# Sheet1.net
KiCad netlist of a schematic drawn in Altium Designer
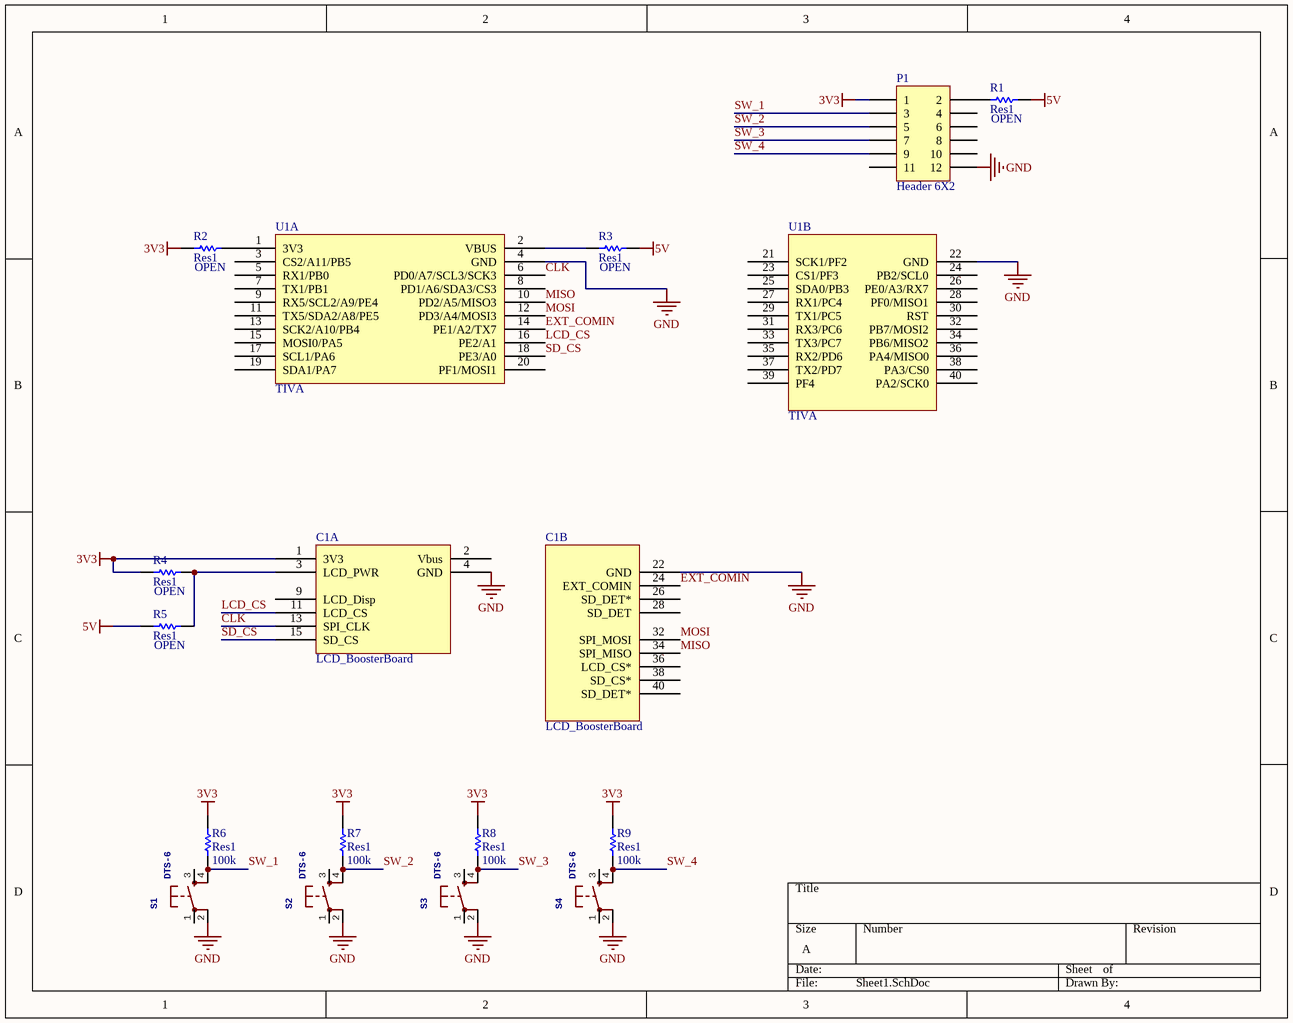
[diagram p0: Sheet1.SchDoc]

(export (version "E")
  (design (tool "Eeschema 10.0.6"))
  (components
    (comp (ref "C1")
      (value "LCD_BoosterBoard")
      (footprint "TIVA")
      (libsource (lib "Schlib1") (part "LCD_BoosterBoard"))
    )
    (comp (ref "P1")
      (value "Header 6X2")
      (footprint "HDR2X6")
      (description "Header, 6-Pin, Dual row")
      (fields (field (name "PUBLISHER") "Altium Limited"))
      (libsource (lib "Miscellaneous Connectors") (part "Header 6X2"))
    )
    (comp (ref "R1")
      (value "Res1")
      (footprint "AXIAL-0.3")
      (description "Resistor")
      (fields (field (name "ALTIUM_VALUE") "OPEN") (field (name "PUBLISHER") "Altium Limited"))
      (libsource (lib "Miscellaneous Devices") (part "Res1"))
    )
    (comp (ref "R2")
      (value "Res1")
      (footprint "AXIAL-0.3")
      (description "Resistor")
      (fields (field (name "ALTIUM_VALUE") "OPEN") (field (name "PUBLISHER") "Altium Limited"))
      (libsource (lib "Miscellaneous Devices") (part "Res1"))
    )
    (comp (ref "R3")
      (value "Res1")
      (footprint "AXIAL-0.3")
      (description "Resistor")
      (fields (field (name "ALTIUM_VALUE") "OPEN") (field (name "PUBLISHER") "Altium Limited"))
      (libsource (lib "Miscellaneous Devices") (part "Res1"))
    )
    (comp (ref "R4")
      (value "Res1")
      (footprint "AXIAL-0.3")
      (description "Resistor")
      (fields (field (name "ALTIUM_VALUE") "OPEN") (field (name "PUBLISHER") "Altium Limited"))
      (libsource (lib "Miscellaneous Devices") (part "Res1"))
    )
    (comp (ref "R5")
      (value "Res1")
      (footprint "AXIAL-0.3")
      (description "Resistor")
      (fields (field (name "ALTIUM_VALUE") "OPEN") (field (name "PUBLISHER") "Altium Limited"))
      (libsource (lib "Miscellaneous Devices") (part "Res1"))
    )
    (comp (ref "R6")
      (value "Res1")
      (footprint "AXIAL-0.3")
      (description "Resistor")
      (fields (field (name "ALTIUM_VALUE") "100k") (field (name "PUBLISHER") "Altium Limited"))
      (libsource (lib "Miscellaneous Devices") (part "Res1"))
    )
    (comp (ref "R7")
      (value "Res1")
      (footprint "AXIAL-0.3")
      (description "Resistor")
      (fields (field (name "ALTIUM_VALUE") "100k") (field (name "PUBLISHER") "Altium Limited"))
      (libsource (lib "Miscellaneous Devices") (part "Res1"))
    )
    (comp (ref "R8")
      (value "Res1")
      (footprint "AXIAL-0.3")
      (description "Resistor")
      (fields (field (name "ALTIUM_VALUE") "100k") (field (name "PUBLISHER") "Altium Limited"))
      (libsource (lib "Miscellaneous Devices") (part "Res1"))
    )
    (comp (ref "R9")
      (value "Res1")
      (footprint "AXIAL-0.3")
      (description "Resistor")
      (fields (field (name "ALTIUM_VALUE") "100k") (field (name "PUBLISHER") "Altium Limited"))
      (libsource (lib "Miscellaneous Devices") (part "Res1"))
    )
    (comp (ref "S1") (value "DTS-6") (footprint "DTS-6") (libsource (lib "Switches") (part "DTS-6")))
    (comp (ref "S2") (value "DTS-6") (footprint "DTS-6") (libsource (lib "Switches") (part "DTS-6")))
    (comp (ref "S3") (value "DTS-6") (footprint "DTS-6") (libsource (lib "Switches") (part "DTS-6")))
    (comp (ref "S4") (value "DTS-6") (footprint "DTS-6") (libsource (lib "Switches") (part "DTS-6")))
    (comp (ref "U1") (value "TIVA") (footprint "TIVA") (libsource (lib "Schlib1") (part "TIVA")))
  )
  (nets
    (net (code "1") (name "/CLK") (class "Default")
      (node (ref "C1") (pin "13") (pinfunction "SPI_CLK_13") (pintype "passive"))
      (node (ref "U1") (pin "6") (pinfunction "PD0/A7/SCL3/SCK3_6") (pintype "passive"))
    )
    (net (code "2") (name "/EXT_COMIN") (class "Default")
      (node (ref "C1") (pin "24") (pinfunction "EXT_COMIN_24") (pintype "passive"))
      (node (ref "U1") (pin "14") (pinfunction "PE1/A2/TX7_14") (pintype "passive"))
    )
    (net (code "3") (name "/LCD_CS") (class "Default")
      (node (ref "C1") (pin "11") (pinfunction "LCD_CS_11") (pintype "passive"))
      (node (ref "U1") (pin "16") (pinfunction "PE2/A1_16") (pintype "passive"))
    )
    (net (code "4") (name "/MISO") (class "Default")
      (node (ref "C1") (pin "34") (pinfunction "SPI_MISO_34") (pintype "passive"))
      (node (ref "U1") (pin "10") (pinfunction "PD2/A5/MISO3_10") (pintype "passive"))
    )
    (net (code "5") (name "/MOSI") (class "Default")
      (node (ref "C1") (pin "32") (pinfunction "SPI_MOSI_32") (pintype "passive"))
      (node (ref "U1") (pin "12") (pinfunction "PD3/A4/MOSI3_12") (pintype "passive"))
    )
    (net (code "6") (name "/SD_CS") (class "Default")
      (node (ref "C1") (pin "15") (pinfunction "SD_CS_15") (pintype "passive"))
      (node (ref "U1") (pin "18") (pinfunction "PE3/A0_18") (pintype "passive"))
    )
    (net (code "7") (name "/SW_1") (class "Default")
      (node (ref "P1") (pin "3") (pinfunction "3_3") (pintype "passive"))
      (node (ref "R6") (pin "1") (pinfunction "1_1") (pintype "passive"))
      (node (ref "S1") (pin "4") (pinfunction "4_4") (pintype "passive"))
    )
    (net (code "8") (name "/SW_2") (class "Default")
      (node (ref "P1") (pin "5") (pinfunction "5_5") (pintype "passive"))
      (node (ref "R7") (pin "1") (pinfunction "1_1") (pintype "passive"))
      (node (ref "S2") (pin "4") (pinfunction "4_4") (pintype "passive"))
    )
    (net (code "9") (name "/SW_3") (class "Default")
      (node (ref "P1") (pin "7") (pinfunction "7_7") (pintype "passive"))
      (node (ref "R8") (pin "1") (pinfunction "1_1") (pintype "passive"))
      (node (ref "S3") (pin "4") (pinfunction "4_4") (pintype "passive"))
    )
    (net (code "10") (name "/SW_4") (class "Default")
      (node (ref "P1") (pin "9") (pinfunction "9_9") (pintype "passive"))
      (node (ref "R9") (pin "1") (pinfunction "1_1") (pintype "passive"))
      (node (ref "S4") (pin "4") (pinfunction "4_4") (pintype "passive"))
    )
    (net (code "11") (name "3V3") (class "Default")
      (node (ref "C1") (pin "1") (pinfunction "3V3_1") (pintype "passive"))
      (node (ref "P1") (pin "1") (pinfunction "1_1") (pintype "passive"))
      (node (ref "R2") (pin "2") (pinfunction "2_2") (pintype "passive"))
      (node (ref "R4") (pin "2") (pinfunction "2_2") (pintype "passive"))
      (node (ref "R6") (pin "2") (pinfunction "2_2") (pintype "passive"))
      (node (ref "R7") (pin "2") (pinfunction "2_2") (pintype "passive"))
      (node (ref "R8") (pin "2") (pinfunction "2_2") (pintype "passive"))
      (node (ref "R9") (pin "2") (pinfunction "2_2") (pintype "passive"))
    )
    (net (code "12") (name "5V") (class "Default")
      (node (ref "R1") (pin "1") (pinfunction "1_1") (pintype "passive"))
      (node (ref "R3") (pin "1") (pinfunction "1_1") (pintype "passive"))
      (node (ref "R5") (pin "2") (pinfunction "2_2") (pintype "passive"))
    )
    (net (code "13") (name "GND") (class "Default")
      (node (ref "C1") (pin "22") (pinfunction "GND_22") (pintype "passive"))
      (node (ref "C1") (pin "4") (pinfunction "GND_4") (pintype "passive"))
      (node (ref "P1") (pin "12") (pinfunction "12_12") (pintype "passive"))
      (node (ref "S1") (pin "2") (pinfunction "2_2") (pintype "passive"))
      (node (ref "S2") (pin "2") (pinfunction "2_2") (pintype "passive"))
      (node (ref "S3") (pin "2") (pinfunction "2_2") (pintype "passive"))
      (node (ref "S4") (pin "2") (pinfunction "2_2") (pintype "passive"))
      (node (ref "U1") (pin "22") (pinfunction "GND_22") (pintype "passive"))
      (node (ref "U1") (pin "4") (pinfunction "GND_4") (pintype "passive"))
    )
    (net (code "14") (name "Net-(C1A-LCD_PWR)") (class "Default")
      (node (ref "C1") (pin "3") (pinfunction "LCD_PWR_3") (pintype "passive"))
      (node (ref "R4") (pin "1") (pinfunction "1_1") (pintype "passive"))
      (node (ref "R5") (pin "1") (pinfunction "1_1") (pintype "passive"))
    )
    (net (code "15") (name "Net-(P1-Pad2)") (class "Default")
      (node (ref "P1") (pin "2") (pinfunction "2_2") (pintype "passive"))
      (node (ref "R1") (pin "2") (pinfunction "2_2") (pintype "passive"))
    )
    (net (code "16") (name "Net-(U1A-3V3)") (class "Default")
      (node (ref "R2") (pin "1") (pinfunction "1_1") (pintype "passive"))
      (node (ref "U1") (pin "1") (pinfunction "3V3_1") (pintype "passive"))
    )
    (net (code "17") (name "Net-(U1A-VBUS)") (class "Default")
      (node (ref "R3") (pin "2") (pinfunction "2_2") (pintype "passive"))
      (node (ref "U1") (pin "2") (pinfunction "VBUS_2") (pintype "passive"))
    )
    (net (code "18") (name "unconnected-(C1A-LCD_Disp-Pad9)") (class "Default")
      (node (ref "C1") (pin "9") (pinfunction "LCD_Disp_9") (pintype "passive"))
    )
    (net (code "19") (name "unconnected-(C1A-Vbus-Pad2)") (class "Default")
      (node (ref "C1") (pin "2") (pinfunction "Vbus_2") (pintype "passive"))
    )
    (net (code "20") (name "unconnected-(C1B-LCD_CS*-Pad36)") (class "Default")
      (node (ref "C1") (pin "36") (pinfunction "LCD_CS*_36") (pintype "passive"))
    )
    (net (code "21") (name "unconnected-(C1B-SD_CS*-Pad38)") (class "Default")
      (node (ref "C1") (pin "38") (pinfunction "SD_CS*_38") (pintype "passive"))
    )
    (net (code "22") (name "unconnected-(C1B-SD_DET*-Pad26)") (class "Default")
      (node (ref "C1") (pin "26") (pinfunction "SD_DET*_26") (pintype "passive"))
    )
    (net (code "23") (name "unconnected-(C1B-SD_DET*-Pad40)") (class "Default")
      (node (ref "C1") (pin "40") (pinfunction "SD_DET*_40") (pintype "passive"))
    )
    (net (code "24") (name "unconnected-(C1B-SD_DET-Pad28)") (class "Default")
      (node (ref "C1") (pin "28") (pinfunction "SD_DET_28") (pintype "passive"))
    )
    (net (code "25") (name "unconnected-(P1-Pad4)") (class "Default")
      (node (ref "P1") (pin "4") (pinfunction "4_4") (pintype "passive"))
    )
    (net (code "26") (name "unconnected-(P1-Pad6)") (class "Default")
      (node (ref "P1") (pin "6") (pinfunction "6_6") (pintype "passive"))
    )
    (net (code "27") (name "unconnected-(P1-Pad8)") (class "Default")
      (node (ref "P1") (pin "8") (pinfunction "8_8") (pintype "passive"))
    )
    (net (code "28") (name "unconnected-(P1-Pad10)") (class "Default")
      (node (ref "P1") (pin "10") (pinfunction "10_10") (pintype "passive"))
    )
    (net (code "29") (name "unconnected-(P1-Pad11)") (class "Default")
      (node (ref "P1") (pin "11") (pinfunction "11_11") (pintype "passive"))
    )
    (net (code "30") (name "unconnected-(S1-Pad1)") (class "Default")
      (node (ref "S1") (pin "1") (pinfunction "1_1") (pintype "passive"))
    )
    (net (code "31") (name "unconnected-(S1-Pad3)") (class "Default")
      (node (ref "S1") (pin "3") (pinfunction "3_3") (pintype "passive"))
    )
    (net (code "32") (name "unconnected-(S2-Pad1)") (class "Default")
      (node (ref "S2") (pin "1") (pinfunction "1_1") (pintype "passive"))
    )
    (net (code "33") (name "unconnected-(S2-Pad3)") (class "Default")
      (node (ref "S2") (pin "3") (pinfunction "3_3") (pintype "passive"))
    )
    (net (code "34") (name "unconnected-(S3-Pad1)") (class "Default")
      (node (ref "S3") (pin "1") (pinfunction "1_1") (pintype "passive"))
    )
    (net (code "35") (name "unconnected-(S3-Pad3)") (class "Default")
      (node (ref "S3") (pin "3") (pinfunction "3_3") (pintype "passive"))
    )
    (net (code "36") (name "unconnected-(S4-Pad1)") (class "Default")
      (node (ref "S4") (pin "1") (pinfunction "1_1") (pintype "passive"))
    )
    (net (code "37") (name "unconnected-(S4-Pad3)") (class "Default")
      (node (ref "S4") (pin "3") (pinfunction "3_3") (pintype "passive"))
    )
    (net (code "38") (name "unconnected-(U1A-CS2{slash}A11{slash}PB5-Pad3)") (class "Default")
      (node (ref "U1") (pin "3") (pinfunction "CS2/A11/PB5_3") (pintype "passive"))
    )
    (net (code "39") (name "unconnected-(U1A-MOSI0{slash}PA5-Pad15)") (class "Default")
      (node (ref "U1") (pin "15") (pinfunction "MOSI0/PA5_15") (pintype "passive"))
    )
    (net (code "40") (name "unconnected-(U1A-PD1{slash}A6{slash}SDA3{slash}CS3-Pad8)") (class "Default")
      (node (ref "U1") (pin "8") (pinfunction "PD1/A6/SDA3/CS3_8") (pintype "passive"))
    )
    (net (code "41") (name "unconnected-(U1A-PF1{slash}MOSI1-Pad20)") (class "Default")
      (node (ref "U1") (pin "20") (pinfunction "PF1/MOSI1_20") (pintype "passive"))
    )
    (net (code "42") (name "unconnected-(U1A-RX1{slash}PB0-Pad5)") (class "Default")
      (node (ref "U1") (pin "5") (pinfunction "RX1/PB0_5") (pintype "passive"))
    )
    (net (code "43") (name "unconnected-(U1A-RX5{slash}SCL2{slash}A9{slash}PE4-Pad9)") (class "Default")
      (node (ref "U1") (pin "9") (pinfunction "RX5/SCL2/A9/PE4_9") (pintype "passive"))
    )
    (net (code "44") (name "unconnected-(U1A-SCK2{slash}A10{slash}PB4-Pad13)") (class "Default")
      (node (ref "U1") (pin "13") (pinfunction "SCK2/A10/PB4_13") (pintype "passive"))
    )
    (net (code "45") (name "unconnected-(U1A-SCL1{slash}PA6-Pad17)") (class "Default")
      (node (ref "U1") (pin "17") (pinfunction "SCL1/PA6_17") (pintype "passive"))
    )
    (net (code "46") (name "unconnected-(U1A-SDA1{slash}PA7-Pad19)") (class "Default")
      (node (ref "U1") (pin "19") (pinfunction "SDA1/PA7_19") (pintype "passive"))
    )
    (net (code "47") (name "unconnected-(U1A-TX1{slash}PB1-Pad7)") (class "Default")
      (node (ref "U1") (pin "7") (pinfunction "TX1/PB1_7") (pintype "passive"))
    )
    (net (code "48") (name "unconnected-(U1A-TX5{slash}SDA2{slash}A8{slash}PE5-Pad11)") (class "Default")
      (node (ref "U1") (pin "11") (pinfunction "TX5/SDA2/A8/PE5_11") (pintype "passive"))
    )
    (net (code "49") (name "unconnected-(U1B-CS1{slash}PF3-Pad23)") (class "Default")
      (node (ref "U1") (pin "23") (pinfunction "CS1/PF3_23") (pintype "passive"))
    )
    (net (code "50") (name "unconnected-(U1B-PA2{slash}SCK0-Pad40)") (class "Default")
      (node (ref "U1") (pin "40") (pinfunction "PA2/SCK0_40") (pintype "passive"))
    )
    (net (code "51") (name "unconnected-(U1B-PA3{slash}CS0-Pad38)") (class "Default")
      (node (ref "U1") (pin "38") (pinfunction "PA3/CS0_38") (pintype "passive"))
    )
    (net (code "52") (name "unconnected-(U1B-PA4{slash}MISO0-Pad36)") (class "Default")
      (node (ref "U1") (pin "36") (pinfunction "PA4/MISO0_36") (pintype "passive"))
    )
    (net (code "53") (name "unconnected-(U1B-PB2{slash}SCL0-Pad24)") (class "Default")
      (node (ref "U1") (pin "24") (pinfunction "PB2/SCL0_24") (pintype "passive"))
    )
    (net (code "54") (name "unconnected-(U1B-PB6{slash}MISO2-Pad34)") (class "Default")
      (node (ref "U1") (pin "34") (pinfunction "PB6/MISO2_34") (pintype "passive"))
    )
    (net (code "55") (name "unconnected-(U1B-PB7{slash}MOSI2-Pad32)") (class "Default")
      (node (ref "U1") (pin "32") (pinfunction "PB7/MOSI2_32") (pintype "passive"))
    )
    (net (code "56") (name "unconnected-(U1B-PE0{slash}A3{slash}RX7-Pad26)") (class "Default")
      (node (ref "U1") (pin "26") (pinfunction "PE0/A3/RX7_26") (pintype "passive"))
    )
    (net (code "57") (name "unconnected-(U1B-PF0{slash}MISO1-Pad28)") (class "Default")
      (node (ref "U1") (pin "28") (pinfunction "PF0/MISO1_28") (pintype "passive"))
    )
    (net (code "58") (name "unconnected-(U1B-PF4-Pad39)") (class "Default")
      (node (ref "U1") (pin "39") (pinfunction "PF4_39") (pintype "passive"))
    )
    (net (code "59") (name "unconnected-(U1B-RST-Pad30)") (class "Default")
      (node (ref "U1") (pin "30") (pinfunction "RST_30") (pintype "passive"))
    )
    (net (code "60") (name "unconnected-(U1B-RX1{slash}PC4-Pad27)") (class "Default")
      (node (ref "U1") (pin "27") (pinfunction "RX1/PC4_27") (pintype "passive"))
    )
    (net (code "61") (name "unconnected-(U1B-RX2{slash}PD6-Pad35)") (class "Default")
      (node (ref "U1") (pin "35") (pinfunction "RX2/PD6_35") (pintype "passive"))
    )
    (net (code "62") (name "unconnected-(U1B-RX3{slash}PC6-Pad31)") (class "Default")
      (node (ref "U1") (pin "31") (pinfunction "RX3/PC6_31") (pintype "passive"))
    )
    (net (code "63") (name "unconnected-(U1B-SCK1{slash}PF2-Pad21)") (class "Default")
      (node (ref "U1") (pin "21") (pinfunction "SCK1/PF2_21") (pintype "passive"))
    )
    (net (code "64") (name "unconnected-(U1B-SDA0{slash}PB3-Pad25)") (class "Default")
      (node (ref "U1") (pin "25") (pinfunction "SDA0/PB3_25") (pintype "passive"))
    )
    (net (code "65") (name "unconnected-(U1B-TX1{slash}PC5-Pad29)") (class "Default")
      (node (ref "U1") (pin "29") (pinfunction "TX1/PC5_29") (pintype "passive"))
    )
    (net (code "66") (name "unconnected-(U1B-TX2{slash}PD7-Pad37)") (class "Default")
      (node (ref "U1") (pin "37") (pinfunction "TX2/PD7_37") (pintype "passive"))
    )
    (net (code "67") (name "unconnected-(U1B-TX3{slash}PC7-Pad33)") (class "Default")
      (node (ref "U1") (pin "33") (pinfunction "TX3/PC7_33") (pintype "passive"))
    )
  )
)
